# SiegeLeanControl.net
KiCad netlist of a schematic drawn in EAGLE
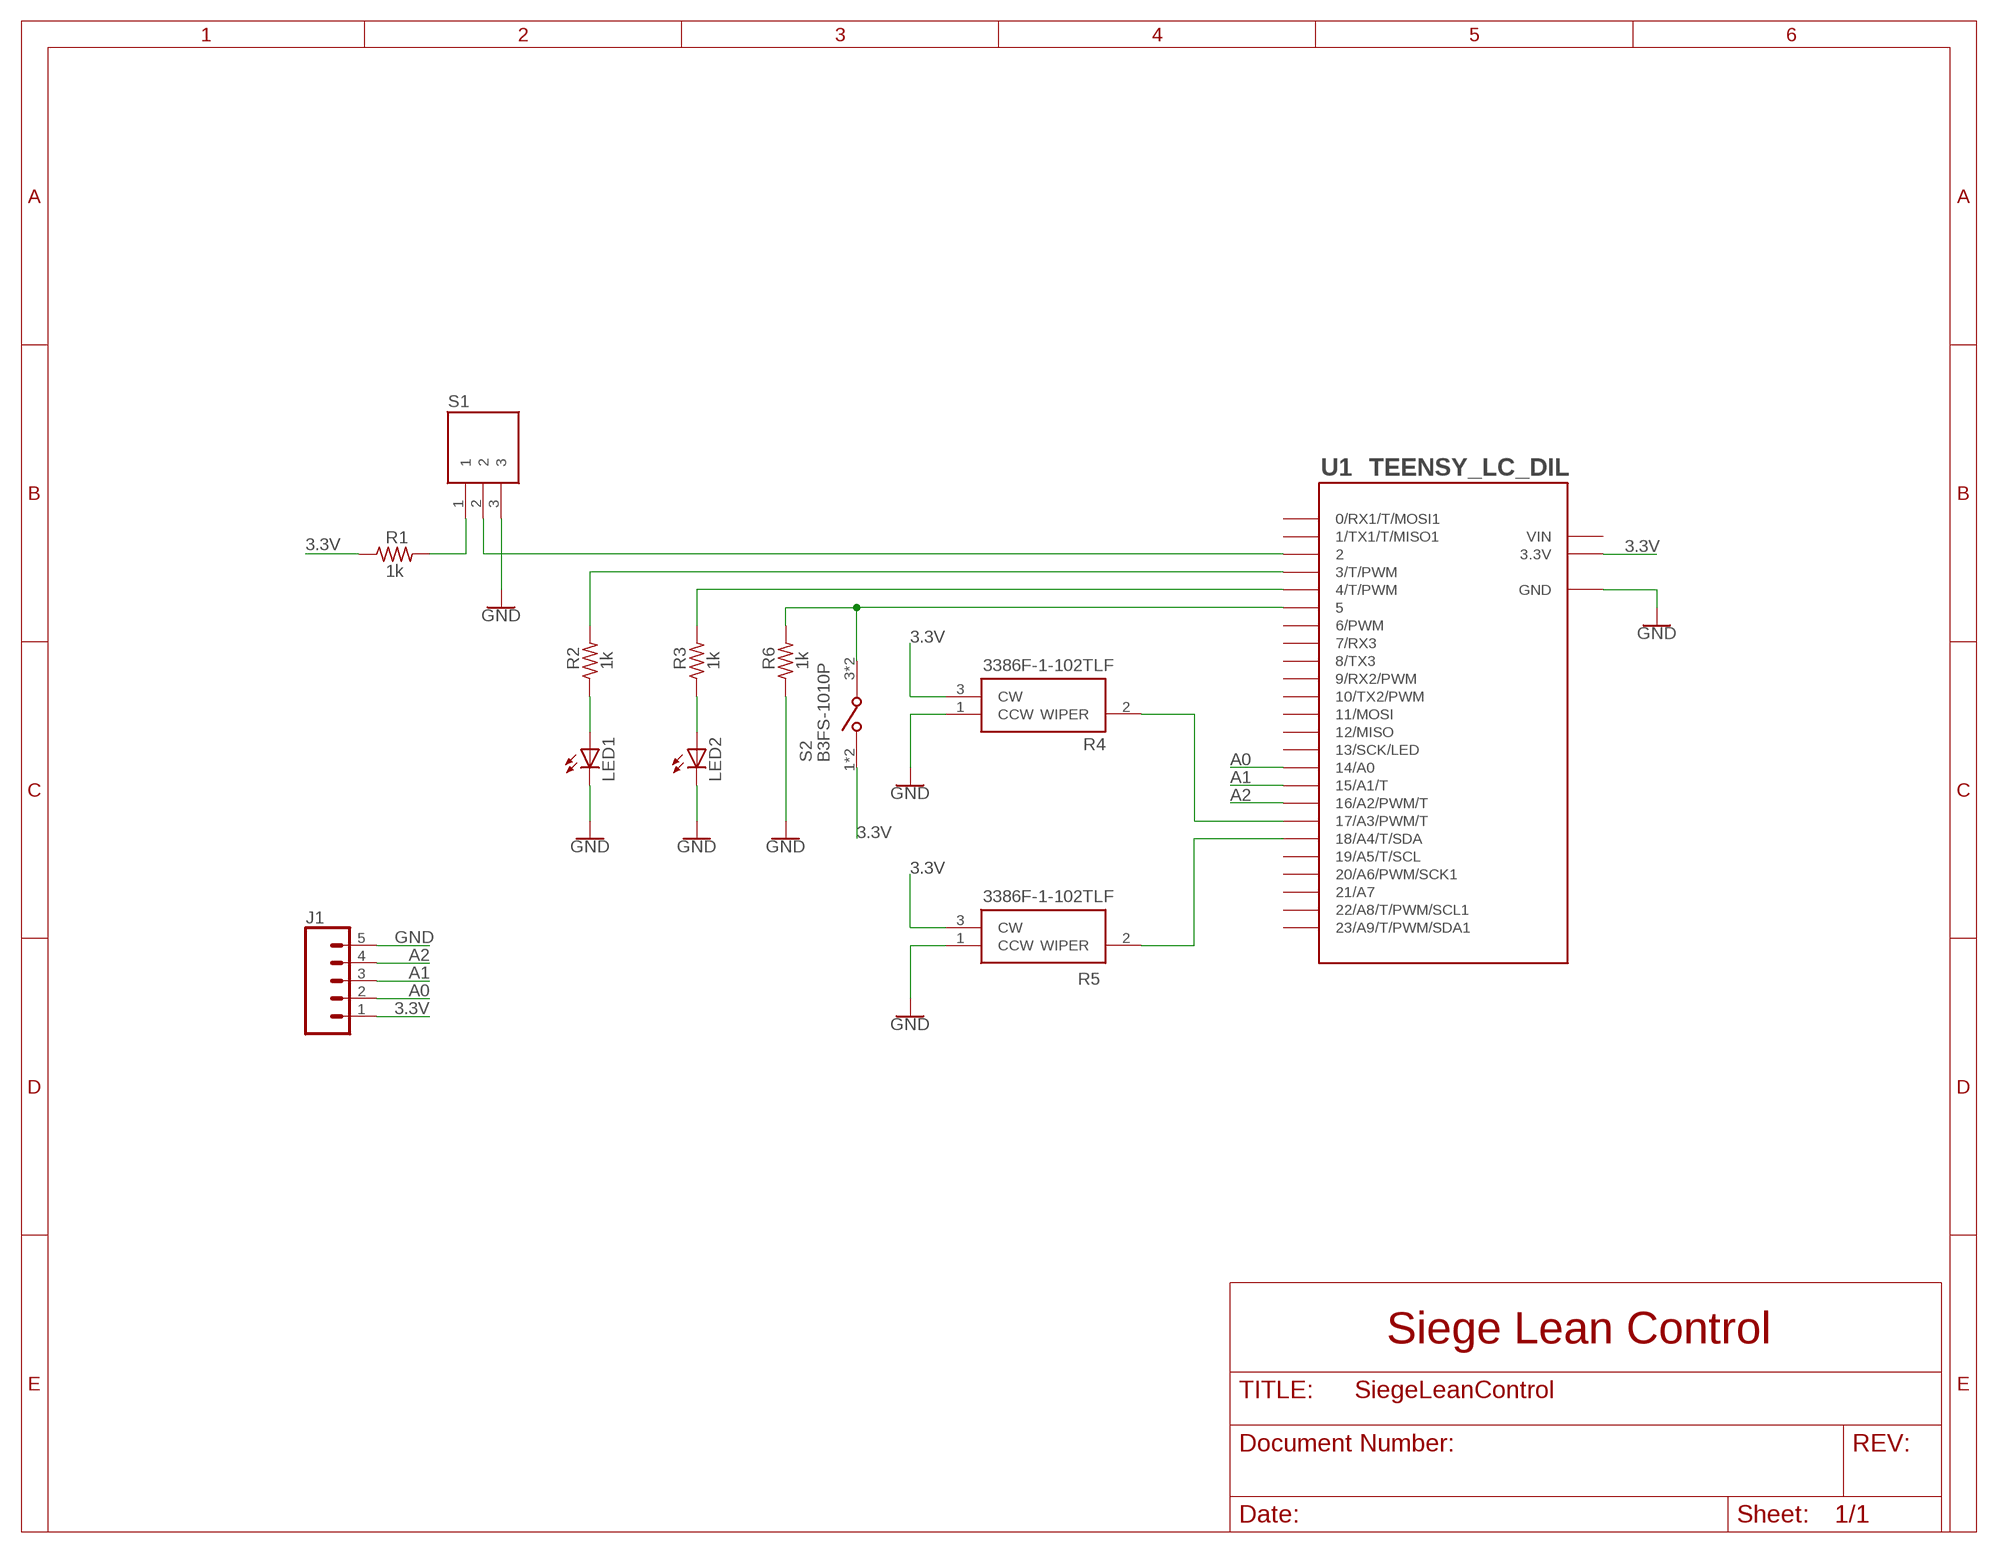
[diagram p0: schematic, sheet 1]

(export (version "E")
  (design (tool "Eeschema 10.0.6"))
  (components
    (comp (ref "J1")
      (value "CONN_05")
      (footprint "eagle-import:1X05")
      (libsource (lib "eagle-import") (part "CONN_05"))
    )
    (comp (ref "LED1")
      (value "LEDCHIPLED_1206")
      (footprint "eagle-import:CHIPLED_1206")
      (libsource (lib "eagle-import") (part "LEDCHIPLED_1206"))
    )
    (comp (ref "LED2")
      (value "LEDCHIPLED_1206")
      (footprint "eagle-import:CHIPLED_1206")
      (libsource (lib "eagle-import") (part "LEDCHIPLED_1206"))
    )
    (comp (ref "R1")
      (value "1k")
      (footprint "eagle-import:R1206")
      (libsource (lib "eagle-import") (part "R-US_R1206"))
    )
    (comp (ref "R2")
      (value "1k")
      (footprint "eagle-import:R1206")
      (libsource (lib "eagle-import") (part "R-US_R1206"))
    )
    (comp (ref "R3")
      (value "1k")
      (footprint "eagle-import:R1206")
      (libsource (lib "eagle-import") (part "R-US_R1206"))
    )
    (comp (ref "R4")
      (value "3386F-1-103TLF")
      (footprint "eagle-import:3386F1103TLF")
      (fields
        (field (name "MOUSER_PART_NUMBER") "652-3386F-1-103TLF")
        (field (name "RS_PART_NUMBER") "5222233P")
      )
      (libsource (lib "eagle-import") (part "3386F-1-103TLF"))
    )
    (comp (ref "R5")
      (value "3386F-1-103TLF")
      (footprint "eagle-import:3386F1103TLF")
      (fields
        (field (name "MOUSER_PART_NUMBER") "652-3386F-1-103TLF")
        (field (name "RS_PART_NUMBER") "5222233P")
      )
      (libsource (lib "eagle-import") (part "3386F-1-103TLF"))
    )
    (comp (ref "R6")
      (value "1k")
      (footprint "eagle-import:R1206")
      (libsource (lib "eagle-import") (part "R-US_R1206"))
    )
    (comp (ref "S1")
      (value "OS102011MA1QN1")
      (footprint "eagle-import:OS102011MA1QN1")
      (fields
        (field (name "MOUSER_PART_NUMBER") "611-OS102011MA1QN1")
        (field (name "RS_PART_NUMBER") "7874855")
      )
      (libsource (lib "eagle-import") (part "OS102011MA1QN1"))
    )
    (comp (ref "S2")
      (value "B3FS-1010P")
      (footprint "eagle-import:SW_B3FS-1010P")
      (fields (field (name "DIGI-KEY_PART_NUMBER") "SW1440CT-ND") (field (name "MF") "Omron Electronics"))
      (libsource (lib "eagle-import") (part "B3FS-1010P"))
    )
    (comp (ref "U1")
      (value "TEENSY_LC_DIL")
      (footprint "eagle-import:TEENSY_3.0-3.2&LC_DIL")
      (libsource (lib "eagle-import") (part "TEENSY_LC_DIL"))
    )
  )
  (nets
    (net (code "1") (name "/3.3V") (class "Default")
      (node (ref "J1") (pin "1") (pinfunction "1_1") (pintype "passive"))
      (node (ref "R1") (pin "1") (pinfunction "1_1") (pintype "passive"))
      (node (ref "R4") (pin "3") (pinfunction "CW_3") (pintype "bidirectional"))
      (node (ref "R5") (pin "3") (pinfunction "CW_3") (pintype "bidirectional"))
      (node (ref "S2") (pin "1") (pinfunction "1_1") (pintype "passive"))
      (node (ref "S2") (pin "2") (pinfunction "1_2") (pintype "passive"))
      (node (ref "U1") (pin "3.3V") (pinfunction "3.3V_3.3V") (pintype "power_in"))
    )
    (net (code "2") (name "/A0") (class "Default")
      (node (ref "J1") (pin "2") (pinfunction "2_2") (pintype "passive"))
      (node (ref "U1") (pin "14/A0") (pinfunction "14/A0_14/A0") (pintype "bidirectional"))
    )
    (net (code "3") (name "/A1") (class "Default")
      (node (ref "J1") (pin "3") (pinfunction "3_3") (pintype "passive"))
      (node (ref "U1") (pin "15/A1") (pinfunction "15/A1/T_15/A1") (pintype "bidirectional"))
    )
    (net (code "4") (name "/A2") (class "Default")
      (node (ref "J1") (pin "4") (pinfunction "4_4") (pintype "passive"))
      (node (ref "U1") (pin "16/A2") (pinfunction "16/A2/PWM/T_16/A2") (pintype "bidirectional"))
    )
    (net (code "5") (name "/VIN") (class "Default")
      (node (ref "U1") (pin "VIN") (pinfunction "VIN_VIN") (pintype "power_in"))
    )
    (net (code "6") (name "GND") (class "Default")
      (node (ref "J1") (pin "5") (pinfunction "5_5") (pintype "passive"))
      (node (ref "LED1") (pin "C") (pinfunction "C_C") (pintype "passive"))
      (node (ref "LED2") (pin "C") (pinfunction "C_C") (pintype "passive"))
      (node (ref "R4") (pin "1") (pinfunction "CCW_1") (pintype "bidirectional"))
      (node (ref "R5") (pin "1") (pinfunction "CCW_1") (pintype "bidirectional"))
      (node (ref "R6") (pin "1") (pinfunction "1_1") (pintype "passive"))
      (node (ref "S1") (pin "3") (pinfunction "3_3") (pintype "bidirectional"))
      (node (ref "U1") (pin "AGND") (pinfunction "GND_AGND") (pintype "power_in"))
      (node (ref "U1") (pin "GND") (pinfunction "GND_GND") (pintype "power_in"))
    )
    (net (code "7") (name "Net-(LED1-PadA)") (class "Default")
      (node (ref "LED1") (pin "A") (pinfunction "A_A") (pintype "passive"))
      (node (ref "R2") (pin "1") (pinfunction "1_1") (pintype "passive"))
    )
    (net (code "8") (name "Net-(LED2-PadA)") (class "Default")
      (node (ref "LED2") (pin "A") (pinfunction "A_A") (pintype "passive"))
      (node (ref "R3") (pin "1") (pinfunction "1_1") (pintype "passive"))
    )
    (net (code "9") (name "Net-(R1-Pad2)") (class "Default")
      (node (ref "R1") (pin "2") (pinfunction "2_2") (pintype "passive"))
      (node (ref "S1") (pin "1") (pinfunction "1_1") (pintype "bidirectional"))
    )
    (net (code "10") (name "Net-(R4-WIPER)") (class "Default")
      (node (ref "R4") (pin "2") (pinfunction "WIPER_2") (pintype "bidirectional"))
      (node (ref "U1") (pin "17/A3") (pinfunction "17/A3/PWM/T_17/A3") (pintype "bidirectional"))
    )
    (net (code "11") (name "Net-(R5-WIPER)") (class "Default")
      (node (ref "R5") (pin "2") (pinfunction "WIPER_2") (pintype "bidirectional"))
      (node (ref "U1") (pin "18/A4") (pinfunction "18/A4/T/SDA_18/A4") (pintype "bidirectional"))
    )
    (net (code "12") (name "Net-(R6-Pad2)") (class "Default")
      (node (ref "R6") (pin "2") (pinfunction "2_2") (pintype "passive"))
      (node (ref "S2") (pin "3") (pinfunction "2_3") (pintype "passive"))
      (node (ref "S2") (pin "4") (pinfunction "2_4") (pintype "passive"))
      (node (ref "U1") (pin "5") (pinfunction "5_5") (pintype "bidirectional"))
    )
    (net (code "13") (name "Net-(S1-Pad2)") (class "Default")
      (node (ref "S1") (pin "2") (pinfunction "2_2") (pintype "bidirectional"))
      (node (ref "U1") (pin "2") (pinfunction "2_2") (pintype "bidirectional"))
    )
    (net (code "14") (name "Net-(U1-3{slash}T{slash}PWM)") (class "Default")
      (node (ref "R2") (pin "2") (pinfunction "2_2") (pintype "passive"))
      (node (ref "U1") (pin "3") (pinfunction "3/T/PWM_3") (pintype "bidirectional"))
    )
    (net (code "15") (name "Net-(U1-4{slash}T{slash}PWM)") (class "Default")
      (node (ref "R3") (pin "2") (pinfunction "2_2") (pintype "passive"))
      (node (ref "U1") (pin "4") (pinfunction "4/T/PWM_4") (pintype "bidirectional"))
    )
    (net (code "16") (name "unconnected-(U1-0{slash}RX1{slash}T{slash}MOSI1-Pad0)") (class "Default")
      (node (ref "U1") (pin "0") (pinfunction "0/RX1/T/MOSI1_0") (pintype "bidirectional"))
    )
    (net (code "17") (name "unconnected-(U1-1{slash}TX1{slash}T{slash}MISO1-Pad1)") (class "Default")
      (node (ref "U1") (pin "1") (pinfunction "1/TX1/T/MISO1_1") (pintype "bidirectional"))
    )
    (net (code "18") (name "unconnected-(U1-6{slash}PWM-Pad6)") (class "Default")
      (node (ref "U1") (pin "6") (pinfunction "6/PWM_6") (pintype "bidirectional"))
    )
    (net (code "19") (name "unconnected-(U1-7{slash}RX3-Pad7)") (class "Default")
      (node (ref "U1") (pin "7") (pinfunction "7/RX3_7") (pintype "bidirectional"))
    )
    (net (code "20") (name "unconnected-(U1-8{slash}TX3-Pad8)") (class "Default")
      (node (ref "U1") (pin "8") (pinfunction "8/TX3_8") (pintype "bidirectional"))
    )
    (net (code "21") (name "unconnected-(U1-9{slash}RX2{slash}PWM-Pad9)") (class "Default")
      (node (ref "U1") (pin "9") (pinfunction "9/RX2/PWM_9") (pintype "bidirectional"))
    )
    (net (code "22") (name "unconnected-(U1-10{slash}TX2{slash}PWM-Pad10)") (class "Default")
      (node (ref "U1") (pin "10") (pinfunction "10/TX2/PWM_10") (pintype "bidirectional"))
    )
    (net (code "23") (name "unconnected-(U1-11{slash}MOSI-Pad11)") (class "Default")
      (node (ref "U1") (pin "11") (pinfunction "11/MOSI_11") (pintype "bidirectional"))
    )
    (net (code "24") (name "unconnected-(U1-12{slash}MISO-Pad12)") (class "Default")
      (node (ref "U1") (pin "12") (pinfunction "12/MISO_12") (pintype "bidirectional"))
    )
    (net (code "25") (name "unconnected-(U1-13{slash}SCK{slash}LED-Pad13)") (class "Default")
      (node (ref "U1") (pin "13") (pinfunction "13/SCK/LED_13") (pintype "bidirectional"))
    )
    (net (code "26") (name "unconnected-(U1-19{slash}A5{slash}T{slash}SCL-Pad19{slash}A5)") (class "Default")
      (node (ref "U1") (pin "19/A5") (pinfunction "19/A5/T/SCL_19/A5") (pintype "bidirectional"))
    )
    (net (code "27") (name "unconnected-(U1-20{slash}A6{slash}PWM{slash}SCK1-Pad20{slash}A6)") (class "Default")
      (node (ref "U1") (pin "20/A6") (pinfunction "20/A6/PWM/SCK1_20/A6") (pintype "bidirectional"))
    )
    (net (code "28") (name "unconnected-(U1-22{slash}A8{slash}T{slash}PWM{slash}SCL1-Pad22{slash}A8)") (class "Default")
      (node (ref "U1") (pin "22/A8") (pinfunction "22/A8/T/PWM/SCL1_22/A8") (pintype "bidirectional"))
    )
    (net (code "29") (name "unconnected-(U1-23{slash}A9{slash}T{slash}PWM{slash}SDA1-Pad23{slash}A9)") (class "Default")
      (node (ref "U1") (pin "23/A9") (pinfunction "23/A9/T/PWM/SDA1_23/A9") (pintype "bidirectional"))
    )
    (net (code "30") (name "unconnected-(U1-Pad21{slash}A7)") (class "Default")
      (node (ref "U1") (pin "21/A7") (pinfunction "21/A7_21/A7") (pintype "bidirectional"))
    )
  )
)
